# Power_Supply.net
KiCad netlist of a schematic drawn in Altium Designer
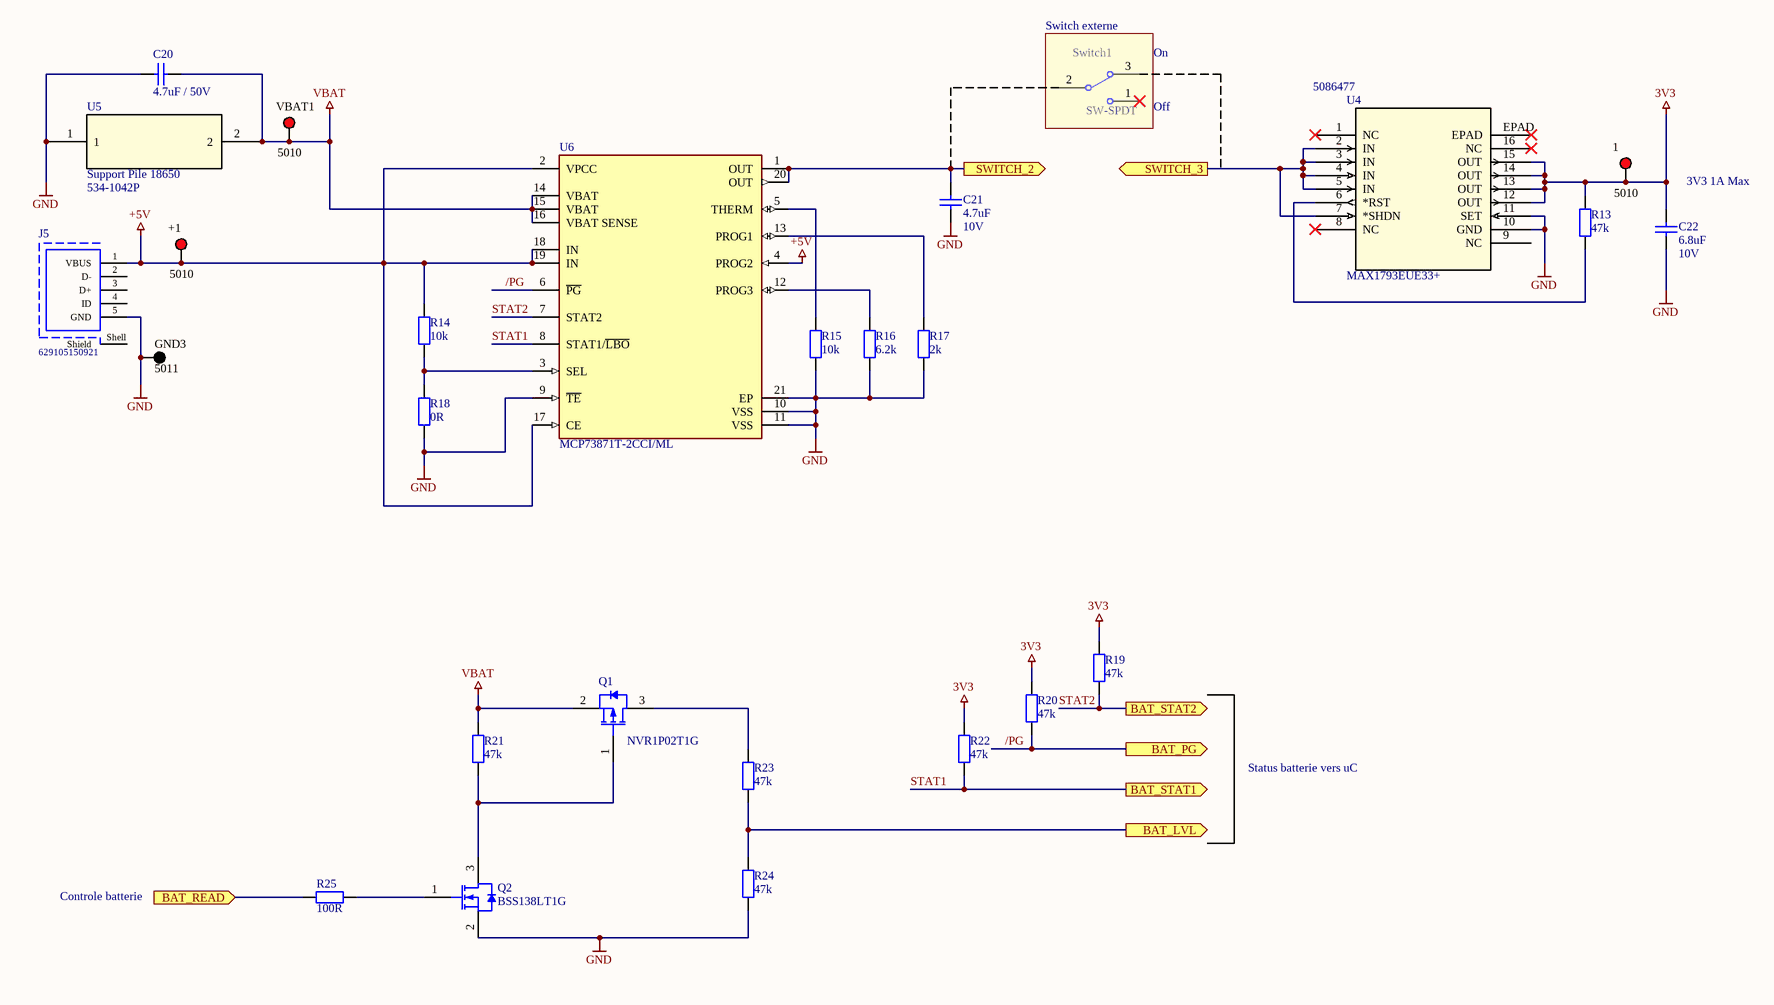
[diagram p0: Power_Supply.SchDoc]

(export (version "E")
  (design (tool "Eeschema 10.0.6"))
  (components
    (comp (ref "+1")
      (value "5010")
      (footprint "KSTN-5010_V")
      (description "Test Point, Red, Through Hole, RoHS, Bulk")
      (fields (field (name "MANUFACTURER") "Keystone"))
      (libsource (lib "Altium Content Vault") (part "TESTPOINT_RED"))
    )
    (comp (ref "1")
      (value "5010")
      (footprint "KSTN-5010_V")
      (description "Test Point, Red, Through Hole, RoHS, Bulk")
      (fields (field (name "MANUFACTURER") "Keystone"))
      (libsource (lib "Altium Content Vault") (part "TESTPOINT_RED"))
    )
    (comp (ref "C20")
      (value "4.7uF / 50V")
      (footprint "CAPC0805")
      (description "Capacitor")
      (fields (field (name "PUBLISHER") "Altium Limited"))
      (libsource (lib "Miscellaneous Devices") (part "Cap"))
    )
    (comp (ref "C21")
      (value "4.7uF")
      (footprint "CAPC0805")
      (description "Capacitor")
      (fields
        (field (name "TENSION") "10V")
        (field (name "Comment") "Cap")
        (field (name "PUBLISHER") "Altium Limited")
      )
      (libsource (lib "Miscellaneous Devices") (part "Cap"))
    )
    (comp (ref "C22")
      (value "6.8uF")
      (footprint "CAPC0805")
      (description "Capacitor")
      (fields
        (field (name "TENSION") "10V")
        (field (name "Comment") "Cap")
        (field (name "PUBLISHER") "Altium Limited")
      )
      (libsource (lib "Miscellaneous Devices") (part "Cap"))
    )
    (comp (ref "GND3")
      (value "5011")
      (footprint "KSTN-5011_V")
      (description "Test Point, Black, Through Hole, RoHS, Bulk")
      (fields (field (name "MANUFACTURER") "Keystone"))
      (libsource (lib "Altium Content Vault") (part "TESTPOINT_BLACK"))
    )
    (comp (ref "J5")
      (value "629105150921")
      (footprint "629105150921")
      (description "Micro USB 2.0 Type AB Receptacle WR-COM, Horizontal, SMT")
      (fields (field (name "MANUFACTURER") "Wurth Elektronik") (field (name "PUBLISHER") "WurthElektronik"))
      (libsource (lib "Altium Content Vault") (part "WE-USB-5-1SHLD"))
    )
    (comp (ref "Q1")
      (value "NVR1P02T1G")
      (footprint "ONSC-SOT-23-3-318-08_V")
      (description "Power MOSFET, -20 V, -1 A, P-Channel, 3-Pin SOT-23, Pb-Free, Tape and Reel")
      (fields (field (name "MANUFACTURER") "On Semiconductor"))
      (libsource (lib "Altium Content Vault") (part "ONSC-PMOS-G1S2D3-3_D"))
    )
    (comp (ref "Q2")
      (value "BSS138LT1G")
      (footprint "ONSC-SOT-23-3-318-08_V")
      (description "Power MOSFET, 200 mA, 50 V, N-Channel, 3-Pin SOT-23, Pb-Free, Tape and Reel")
      (fields (field (name "MANUFACTURER") "On Semiconductor"))
      (libsource (lib "Altium Content Vault") (part "ONSC-NMOS-G1S2D3-3"))
    )
    (comp (ref "R13")
      (value "47k")
      (footprint "RESC0805")
      (description "Resistor")
      (fields (field (name "Comment") "VALUE"))
      (libsource (lib "Support_BAT_1043") (part "RES"))
    )
    (comp (ref "R14")
      (value "10k")
      (footprint "RESC0805")
      (description "Resistor")
      (fields (field (name "Comment") "VALUE"))
      (libsource (lib "Support_BAT_1043") (part "RES"))
    )
    (comp (ref "R15")
      (value "10k")
      (footprint "RESC0805")
      (description "Resistor")
      (fields (field (name "Comment") "VALUE"))
      (libsource (lib "Support_BAT_1043") (part "RES"))
    )
    (comp (ref "R16")
      (value "6.2k")
      (footprint "RESC0805")
      (description "Resistor")
      (fields (field (name "Comment") "VALUE"))
      (libsource (lib "Support_BAT_1043") (part "RES"))
    )
    (comp (ref "R17")
      (value "2k")
      (footprint "RESC0805")
      (description "Resistor")
      (fields (field (name "Comment") "VALUE"))
      (libsource (lib "Support_BAT_1043") (part "RES"))
    )
    (comp (ref "R18")
      (value "0R")
      (footprint "RESC0805")
      (description "Resistor")
      (fields (field (name "Comment") "VALUE"))
      (libsource (lib "Support_BAT_1043") (part "RES"))
    )
    (comp (ref "R19")
      (value "47k")
      (footprint "RESC0805")
      (description "Resistor")
      (fields (field (name "Comment") "VALUE"))
      (libsource (lib "Support_BAT_1043") (part "RES"))
    )
    (comp (ref "R20")
      (value "47k")
      (footprint "RESC0805")
      (description "Resistor")
      (fields (field (name "Comment") "VALUE"))
      (libsource (lib "Support_BAT_1043") (part "RES"))
    )
    (comp (ref "R21")
      (value "47k")
      (footprint "RESC0805")
      (description "Resistor")
      (fields (field (name "Comment") "VALUE"))
      (libsource (lib "") (part "RES_1"))
    )
    (comp (ref "R22")
      (value "47k")
      (footprint "RESC0805")
      (description "Resistor")
      (fields (field (name "Comment") "VALUE"))
      (libsource (lib "Support_BAT_1043") (part "RES"))
    )
    (comp (ref "R23")
      (value "47k")
      (footprint "RESC0805")
      (description "Resistor")
      (fields (field (name "Comment") "VALUE"))
      (libsource (lib "Support_BAT_1043") (part "RES"))
    )
    (comp (ref "R24")
      (value "47k")
      (footprint "RESC0805")
      (description "Resistor")
      (fields (field (name "Comment") "VALUE"))
      (libsource (lib "Support_BAT_1043") (part "RES"))
    )
    (comp (ref "R25")
      (value "100R")
      (footprint "RESC0805")
      (description "Resistor")
      (fields (field (name "Comment") "VALUE"))
      (libsource (lib "") (part "RES_2"))
    )
    (comp (ref "Switch1")
      (value "SW-SPDT")
      (footprint "TL36WW15050")
      (description "SPDT Subminiature Toggle Switch, Right Angle Mounting, Vertical Actuation")
      (fields (field (name "PUBLISHER") "Altium Limited"))
      (libsource (lib "Miscellaneous Devices") (part "SW-SPDT"))
    )
    (comp (ref "U4")
      (value "MAX1793EUE33+")
      (footprint "21-0108_U16E+3_MXM")
      (description "Fixed/Adjustable Positive LDO Regulator, 1.25V Min, 5V Max, 0.35V Dropout, PMOS, PDSO16")
      (fields
        (field (name "SUPPLIER PART NUMBER 1") "5086477")
        (field (name "COPYRIGHT") "Copyright (C) 2021 Ultra Librarian. All rights reserved.")
      )
      (libsource (lib "MAX1793EUE33&plus_") (part "MAX1793EUE33+"))
    )
    (comp (ref "U5")
      (value "Support Pile 18650")
      (footprint "FP-1042P-MFG")
      (description "No Description Available")
      (fields (field (name "SUPPLIER PART NUMBER 1") "534-1042P"))
      (libsource (lib "Support_BAT_1043") (part "1042P"))
    )
    (comp (ref "U6")
      (value "MCP73871T-2CCI/ML")
      (footprint "FP-C04-126-IPC_C")
      (description "IC USB/AC BATT CHRGR W/PPM 20QFN")
      (libsource (lib "Altium Content Vault") (part "b0f216601a400a2976e0698385bc2c7"))
    )
    (comp (ref "VBAT1")
      (value "5010")
      (footprint "KSTN-5010_V")
      (description "Test Point, Red, Through Hole, RoHS, Bulk")
      (fields (field (name "MANUFACTURER") "Keystone"))
      (libsource (lib "Altium Content Vault") (part "TESTPOINT_RED"))
    )
  )
  (nets
    (net (code "1") (name "+5V") (class "Default")
      (node (ref "+1") (pin "1") (pinfunction "1_1") (pintype "passive"))
      (node (ref "J5") (pin "1") (pinfunction "VBUS_1") (pintype "passive"))
      (node (ref "R14") (pin "2") (pinfunction "2_2") (pintype "passive"))
      (node (ref "U6") (pin "17") (pinfunction "CE_17") (pintype "input"))
      (node (ref "U6") (pin "18") (pinfunction "IN_18") (pintype "power_in"))
      (node (ref "U6") (pin "19") (pinfunction "IN_19") (pintype "power_in"))
      (node (ref "U6") (pin "2") (pinfunction "VPCC_2") (pintype "power_in"))
      (node (ref "U6") (pin "4") (pinfunction "PROG2_4") (pintype "input"))
    )
    (net (code "2") (name "/BAT_LVL") (class "Default")
      (node (ref "R23") (pin "1") (pinfunction "1_1") (pintype "passive"))
      (node (ref "R24") (pin "2") (pinfunction "2_2") (pintype "passive"))
    )
    (net (code "3") (name "/BAT_READ") (class "Default")
      (node (ref "R25") (pin "1") (pinfunction "1_1") (pintype "passive"))
    )
    (net (code "4") (name "/STAT1") (class "Default")
      (node (ref "R22") (pin "1") (pinfunction "1_1") (pintype "passive"))
      (node (ref "U6") (pin "8") (pinfunction "STAT1/~{LBO}_8") (pintype "open_collector"))
    )
    (net (code "5") (name "/STAT2") (class "Default")
      (node (ref "R19") (pin "1") (pinfunction "1_1") (pintype "passive"))
      (node (ref "U6") (pin "7") (pinfunction "STAT2_7") (pintype "open_collector"))
    )
    (net (code "6") (name "/SWITCH_2") (class "Default")
      (node (ref "C21") (pin "2") (pinfunction "2_2") (pintype "passive"))
      (node (ref "U6") (pin "1") (pinfunction "OUT_1") (pintype "passive"))
      (node (ref "U6") (pin "20") (pinfunction "OUT_20") (pintype "output"))
    )
    (net (code "7") (name "/SWITCH_3") (class "Default")
      (node (ref "U4") (pin "2") (pinfunction "IN_2") (pintype "passive"))
      (node (ref "U4") (pin "3") (pinfunction "IN_3") (pintype "passive"))
      (node (ref "U4") (pin "4") (pinfunction "IN_4") (pintype "input"))
      (node (ref "U4") (pin "5") (pinfunction "IN_5") (pintype "passive"))
      (node (ref "U4") (pin "7") (pinfunction "*SHDN_7") (pintype "input"))
    )
    (net (code "8") (name "/{slash}PG") (class "Default")
      (node (ref "R20") (pin "1") (pinfunction "1_1") (pintype "passive"))
      (node (ref "U6") (pin "6") (pinfunction "~{PG}_6") (pintype "open_collector"))
    )
    (net (code "9") (name "3V3") (class "Default")
      (node (ref "1") (pin "1") (pinfunction "1_1") (pintype "passive"))
      (node (ref "C22") (pin "2") (pinfunction "2_2") (pintype "passive"))
      (node (ref "R13") (pin "2") (pinfunction "2_2") (pintype "passive"))
      (node (ref "R19") (pin "2") (pinfunction "2_2") (pintype "passive"))
      (node (ref "R20") (pin "2") (pinfunction "2_2") (pintype "passive"))
      (node (ref "R22") (pin "2") (pinfunction "2_2") (pintype "passive"))
      (node (ref "U4") (pin "12") (pinfunction "OUT_12") (pintype "passive"))
      (node (ref "U4") (pin "13") (pinfunction "OUT_13") (pintype "passive"))
      (node (ref "U4") (pin "14") (pinfunction "OUT_14") (pintype "passive"))
      (node (ref "U4") (pin "15") (pinfunction "OUT_15") (pintype "passive"))
    )
    (net (code "10") (name "GND") (class "Default")
      (node (ref "C20") (pin "1") (pinfunction "1_1") (pintype "passive"))
      (node (ref "C21") (pin "1") (pinfunction "1_1") (pintype "passive"))
      (node (ref "C22") (pin "1") (pinfunction "1_1") (pintype "passive"))
      (node (ref "GND3") (pin "1") (pinfunction "1_1") (pintype "passive"))
      (node (ref "J5") (pin "5") (pinfunction "GND_5") (pintype "passive"))
      (node (ref "Q2") (pin "2") (pinfunction "S_2") (pintype "passive"))
      (node (ref "R15") (pin "1") (pinfunction "1_1") (pintype "passive"))
      (node (ref "R16") (pin "1") (pinfunction "1_1") (pintype "passive"))
      (node (ref "R17") (pin "1") (pinfunction "1_1") (pintype "passive"))
      (node (ref "R18") (pin "1") (pinfunction "1_1") (pintype "passive"))
      (node (ref "R24") (pin "1") (pinfunction "1_1") (pintype "passive"))
      (node (ref "U4") (pin "10") (pinfunction "GND_10") (pintype "passive"))
      (node (ref "U4") (pin "11") (pinfunction "SET_11") (pintype "input"))
      (node (ref "U5") (pin "1") (pinfunction "1_1") (pintype "passive"))
      (node (ref "U6") (pin "10") (pinfunction "VSS_10") (pintype "passive"))
      (node (ref "U6") (pin "11") (pinfunction "VSS_11") (pintype "passive"))
      (node (ref "U6") (pin "21") (pinfunction "EP_21") (pintype "passive"))
      (node (ref "U6") (pin "9") (pinfunction "~{TE}_9") (pintype "input"))
    )
    (net (code "11") (name "Net-(Q1-D)") (class "Default")
      (node (ref "Q1") (pin "3") (pinfunction "D_3") (pintype "passive"))
      (node (ref "R23") (pin "2") (pinfunction "2_2") (pintype "passive"))
    )
    (net (code "12") (name "Net-(Q1-G)") (class "Default")
      (node (ref "Q1") (pin "1") (pinfunction "G_1") (pintype "passive"))
      (node (ref "Q2") (pin "3") (pinfunction "D_3") (pintype "passive"))
      (node (ref "R21") (pin "2") (pinfunction "2_2") (pintype "passive"))
    )
    (net (code "13") (name "Net-(Q2-G)") (class "Default")
      (node (ref "Q2") (pin "1") (pinfunction "G_1") (pintype "passive"))
      (node (ref "R25") (pin "2") (pinfunction "2_2") (pintype "passive"))
    )
    (net (code "14") (name "Net-(U4-*RST)") (class "Default")
      (node (ref "R13") (pin "1") (pinfunction "1_1") (pintype "passive"))
      (node (ref "U4") (pin "6") (pinfunction "*RST_6") (pintype "output"))
    )
    (net (code "15") (name "Net-(U6-PROG1)") (class "Default")
      (node (ref "R17") (pin "2") (pinfunction "2_2") (pintype "passive"))
      (node (ref "U6") (pin "13") (pinfunction "PROG1_13") (pintype "bidirectional"))
    )
    (net (code "16") (name "Net-(U6-PROG3)") (class "Default")
      (node (ref "R16") (pin "2") (pinfunction "2_2") (pintype "passive"))
      (node (ref "U6") (pin "12") (pinfunction "PROG3_12") (pintype "bidirectional"))
    )
    (net (code "17") (name "Net-(U6-SEL)") (class "Default")
      (node (ref "R14") (pin "1") (pinfunction "1_1") (pintype "passive"))
      (node (ref "R18") (pin "2") (pinfunction "2_2") (pintype "passive"))
      (node (ref "U6") (pin "3") (pinfunction "SEL_3") (pintype "input"))
    )
    (net (code "18") (name "Net-(U6-THERM)") (class "Default")
      (node (ref "R15") (pin "2") (pinfunction "2_2") (pintype "passive"))
      (node (ref "U6") (pin "5") (pinfunction "THERM_5") (pintype "bidirectional"))
    )
    (net (code "19") (name "VBAT") (class "Default")
      (node (ref "C20") (pin "2") (pinfunction "2_2") (pintype "passive"))
      (node (ref "Q1") (pin "2") (pinfunction "S_2") (pintype "passive"))
      (node (ref "R21") (pin "1") (pinfunction "1_1") (pintype "passive"))
      (node (ref "U5") (pin "2") (pinfunction "2_2") (pintype "passive"))
      (node (ref "U6") (pin "14") (pinfunction "VBAT_14") (pintype "power_in"))
      (node (ref "U6") (pin "15") (pinfunction "VBAT_15") (pintype "power_in"))
      (node (ref "U6") (pin "16") (pinfunction "VBAT_SENSE_16") (pintype "power_in"))
      (node (ref "VBAT1") (pin "1") (pinfunction "1_1") (pintype "passive"))
    )
    (net (code "20") (name "unconnected-(J5-D+-Pad3)") (class "Default")
      (node (ref "J5") (pin "3") (pinfunction "D+_3") (pintype "passive"))
    )
    (net (code "21") (name "unconnected-(J5-D--Pad2)") (class "Default")
      (node (ref "J5") (pin "2") (pinfunction "D-_2") (pintype "passive"))
    )
    (net (code "22") (name "unconnected-(J5-ID-Pad4)") (class "Default")
      (node (ref "J5") (pin "4") (pinfunction "ID_4") (pintype "passive"))
    )
    (net (code "23") (name "unconnected-(J5-Shield-PadShell)") (class "Default")
      (node (ref "J5") (pin "Shell") (pinfunction "Shield_Shell") (pintype "passive"))
    )
    (net (code "24") (name "unconnected-(Switch1-Pad1)") (class "Default")
      (node (ref "Switch1") (pin "1") (pinfunction "1_1") (pintype "passive+no_connect"))
    )
    (net (code "25") (name "unconnected-(Switch1-Pad2)") (class "Default")
      (node (ref "Switch1") (pin "2") (pinfunction "2_2") (pintype "passive"))
    )
    (net (code "26") (name "unconnected-(Switch1-Pad3)") (class "Default")
      (node (ref "Switch1") (pin "3") (pinfunction "3_3") (pintype "passive"))
    )
    (net (code "27") (name "unconnected-(U4-NC-Pad1)") (class "Default")
      (node (ref "U4") (pin "1") (pinfunction "NC_1") (pintype "passive+no_connect"))
    )
    (net (code "28") (name "unconnected-(U4-NC-Pad8)") (class "Default")
      (node (ref "U4") (pin "8") (pinfunction "NC_8") (pintype "passive+no_connect"))
    )
    (net (code "29") (name "unconnected-(U4-NC-Pad9)") (class "Default")
      (node (ref "U4") (pin "9") (pinfunction "NC_9") (pintype "passive"))
    )
    (net (code "30") (name "unconnected-(U4-NC-Pad16)") (class "Default")
      (node (ref "U4") (pin "16") (pinfunction "NC_16") (pintype "passive+no_connect"))
    )
    (net (code "31") (name "unconnected-(U4-PadEPAD)") (class "Default")
      (node (ref "U4") (pin "EPAD") (pinfunction "EPAD_EPAD") (pintype "passive+no_connect"))
    )
  )
)
